# AD9959.net
KiCad netlist of a schematic drawn in Altium Designer
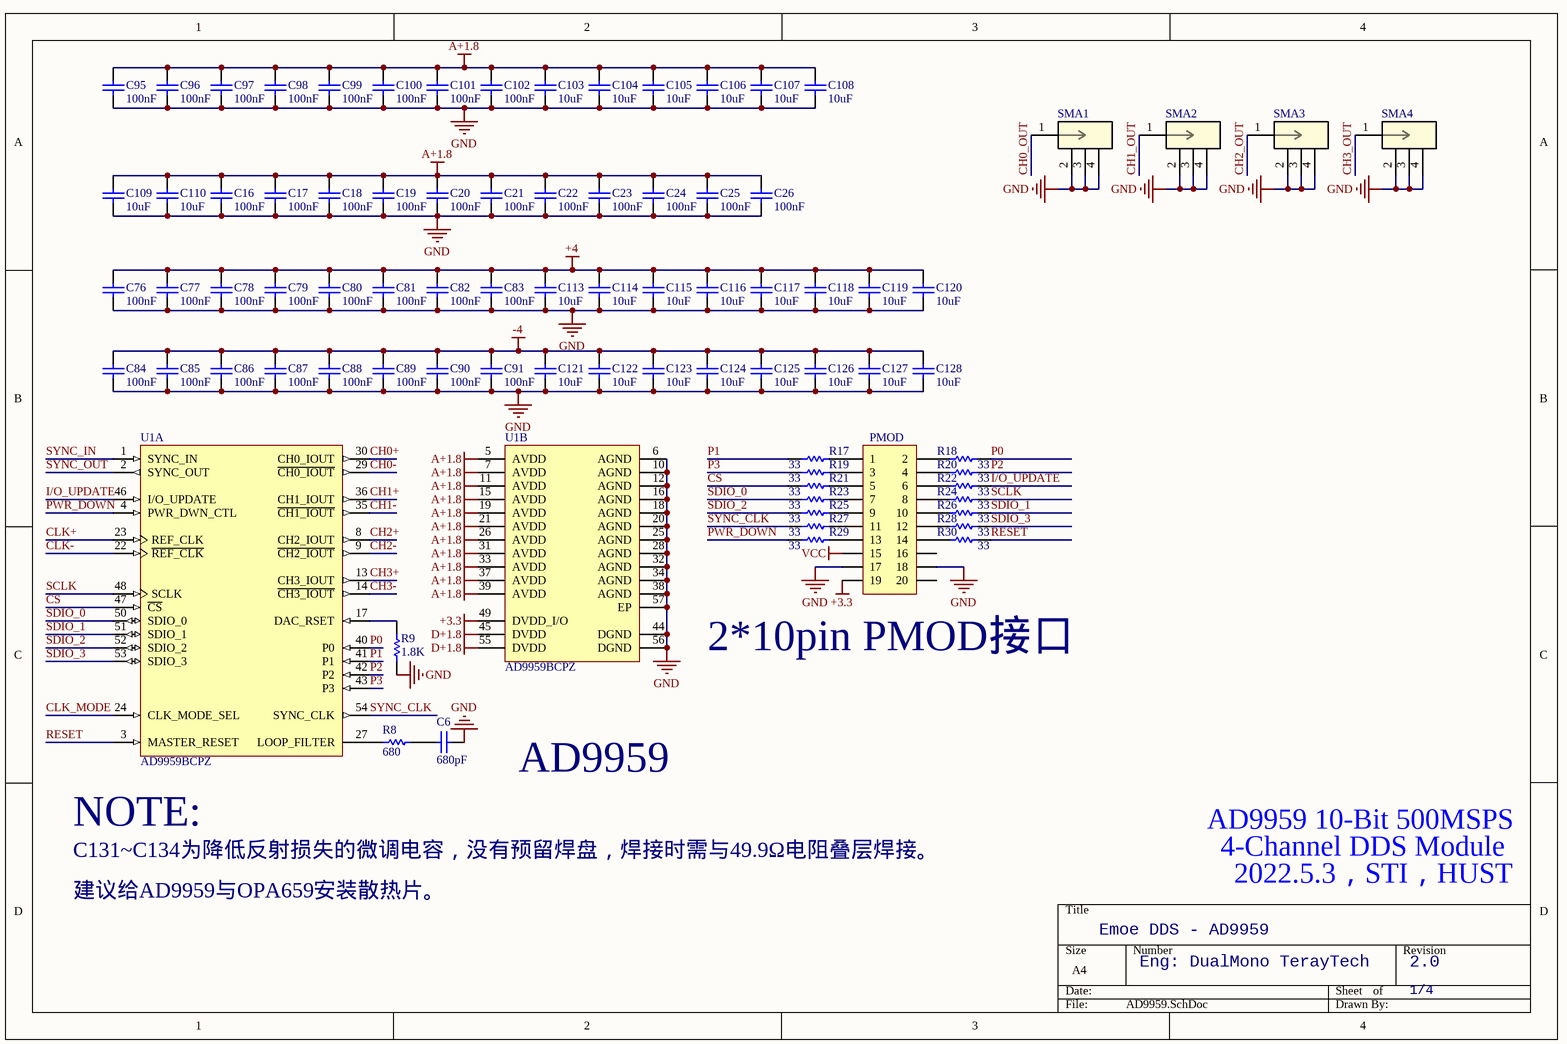
[diagram p0: AD9959.SchDoc]

(export (version "E")
  (design (tool "Eeschema 10.0.6"))
  (components
    (comp (ref "C6")
      (value "680pF")
      (footprint "0402")
      (description "Capacitor")
      (fields (field (name "PUBLISHER") "Altium Limited"))
      (libsource (lib "My Footprint") (part "CAP"))
    )
    (comp (ref "C16")
      (value "100nF")
      (footprint "0402")
      (description "Capacitor")
      (fields (field (name "PUBLISHER") "Altium Limited"))
      (libsource (lib "My Footprint") (part "CAP"))
    )
    (comp (ref "C17")
      (value "100nF")
      (footprint "0402")
      (description "Capacitor")
      (fields (field (name "PUBLISHER") "Altium Limited"))
      (libsource (lib "My Footprint") (part "CAP"))
    )
    (comp (ref "C18")
      (value "100nF")
      (footprint "0402")
      (description "Capacitor")
      (fields (field (name "PUBLISHER") "Altium Limited"))
      (libsource (lib "My Footprint") (part "CAP"))
    )
    (comp (ref "C19")
      (value "100nF")
      (footprint "0402")
      (description "Capacitor")
      (fields (field (name "PUBLISHER") "Altium Limited"))
      (libsource (lib "My Footprint") (part "CAP"))
    )
    (comp (ref "C20")
      (value "100nF")
      (footprint "0402")
      (description "Capacitor")
      (fields (field (name "PUBLISHER") "Altium Limited"))
      (libsource (lib "My Footprint") (part "CAP"))
    )
    (comp (ref "C21")
      (value "100nF")
      (footprint "0402")
      (description "Capacitor")
      (fields (field (name "PUBLISHER") "Altium Limited"))
      (libsource (lib "My Footprint") (part "CAP"))
    )
    (comp (ref "C22")
      (value "100nF")
      (footprint "0402")
      (description "Capacitor")
      (fields (field (name "PUBLISHER") "Altium Limited"))
      (libsource (lib "My Footprint") (part "CAP"))
    )
    (comp (ref "C23")
      (value "100nF")
      (footprint "0402")
      (description "Capacitor")
      (fields (field (name "PUBLISHER") "Altium Limited"))
      (libsource (lib "My Footprint") (part "CAP"))
    )
    (comp (ref "C24")
      (value "100nF")
      (footprint "0402")
      (description "Capacitor")
      (fields (field (name "PUBLISHER") "Altium Limited"))
      (libsource (lib "My Footprint") (part "CAP"))
    )
    (comp (ref "C25")
      (value "100nF")
      (footprint "0402")
      (description "Capacitor")
      (fields (field (name "PUBLISHER") "Altium Limited"))
      (libsource (lib "My Footprint") (part "CAP"))
    )
    (comp (ref "C26")
      (value "100nF")
      (footprint "0402")
      (description "Capacitor")
      (fields (field (name "PUBLISHER") "Altium Limited"))
      (libsource (lib "My Footprint") (part "CAP"))
    )
    (comp (ref "C76")
      (value "100nF")
      (footprint "0402")
      (description "Capacitor")
      (fields (field (name "PUBLISHER") "Altium Limited"))
      (libsource (lib "My Footprint") (part "CAP"))
    )
    (comp (ref "C77")
      (value "100nF")
      (footprint "0402")
      (description "Capacitor")
      (fields (field (name "PUBLISHER") "Altium Limited"))
      (libsource (lib "My Footprint") (part "CAP"))
    )
    (comp (ref "C78")
      (value "100nF")
      (footprint "0402")
      (description "Capacitor")
      (fields (field (name "PUBLISHER") "Altium Limited"))
      (libsource (lib "My Footprint") (part "CAP"))
    )
    (comp (ref "C79")
      (value "100nF")
      (footprint "0402")
      (description "Capacitor")
      (fields (field (name "PUBLISHER") "Altium Limited"))
      (libsource (lib "My Footprint") (part "CAP"))
    )
    (comp (ref "C80")
      (value "100nF")
      (footprint "0402")
      (description "Capacitor")
      (fields (field (name "PUBLISHER") "Altium Limited"))
      (libsource (lib "My Footprint") (part "CAP"))
    )
    (comp (ref "C81")
      (value "100nF")
      (footprint "0402")
      (description "Capacitor")
      (fields (field (name "PUBLISHER") "Altium Limited"))
      (libsource (lib "My Footprint") (part "CAP"))
    )
    (comp (ref "C82")
      (value "100nF")
      (footprint "0402")
      (description "Capacitor")
      (fields (field (name "PUBLISHER") "Altium Limited"))
      (libsource (lib "My Footprint") (part "CAP"))
    )
    (comp (ref "C83")
      (value "100nF")
      (footprint "0402")
      (description "Capacitor")
      (fields (field (name "PUBLISHER") "Altium Limited"))
      (libsource (lib "My Footprint") (part "CAP"))
    )
    (comp (ref "C84")
      (value "100nF")
      (footprint "0402")
      (description "Capacitor")
      (fields (field (name "PUBLISHER") "Altium Limited"))
      (libsource (lib "My Footprint") (part "CAP"))
    )
    (comp (ref "C85")
      (value "100nF")
      (footprint "0402")
      (description "Capacitor")
      (fields (field (name "PUBLISHER") "Altium Limited"))
      (libsource (lib "My Footprint") (part "CAP"))
    )
    (comp (ref "C86")
      (value "100nF")
      (footprint "0402")
      (description "Capacitor")
      (fields (field (name "PUBLISHER") "Altium Limited"))
      (libsource (lib "My Footprint") (part "CAP"))
    )
    (comp (ref "C87")
      (value "100nF")
      (footprint "0402")
      (description "Capacitor")
      (fields (field (name "PUBLISHER") "Altium Limited"))
      (libsource (lib "My Footprint") (part "CAP"))
    )
    (comp (ref "C88")
      (value "100nF")
      (footprint "0402")
      (description "Capacitor")
      (fields (field (name "PUBLISHER") "Altium Limited"))
      (libsource (lib "My Footprint") (part "CAP"))
    )
    (comp (ref "C89")
      (value "100nF")
      (footprint "0402")
      (description "Capacitor")
      (fields (field (name "PUBLISHER") "Altium Limited"))
      (libsource (lib "My Footprint") (part "CAP"))
    )
    (comp (ref "C90")
      (value "100nF")
      (footprint "0402")
      (description "Capacitor")
      (fields (field (name "PUBLISHER") "Altium Limited"))
      (libsource (lib "My Footprint") (part "CAP"))
    )
    (comp (ref "C91")
      (value "100nF")
      (footprint "0402")
      (description "Capacitor")
      (fields (field (name "PUBLISHER") "Altium Limited"))
      (libsource (lib "My Footprint") (part "CAP"))
    )
    (comp (ref "C95")
      (value "100nF")
      (footprint "0402")
      (description "Capacitor")
      (fields (field (name "PUBLISHER") "Altium Limited"))
      (libsource (lib "My Footprint") (part "CAP"))
    )
    (comp (ref "C96")
      (value "100nF")
      (footprint "0402")
      (description "Capacitor")
      (fields (field (name "PUBLISHER") "Altium Limited"))
      (libsource (lib "My Footprint") (part "CAP"))
    )
    (comp (ref "C97")
      (value "100nF")
      (footprint "0402")
      (description "Capacitor")
      (fields (field (name "PUBLISHER") "Altium Limited"))
      (libsource (lib "My Footprint") (part "CAP"))
    )
    (comp (ref "C98")
      (value "100nF")
      (footprint "0402")
      (description "Capacitor")
      (fields (field (name "PUBLISHER") "Altium Limited"))
      (libsource (lib "My Footprint") (part "CAP"))
    )
    (comp (ref "C99")
      (value "100nF")
      (footprint "0402")
      (description "Capacitor")
      (fields (field (name "PUBLISHER") "Altium Limited"))
      (libsource (lib "My Footprint") (part "CAP"))
    )
    (comp (ref "C100")
      (value "100nF")
      (footprint "0402")
      (description "Capacitor")
      (fields (field (name "PUBLISHER") "Altium Limited"))
      (libsource (lib "My Footprint") (part "CAP"))
    )
    (comp (ref "C101")
      (value "100nF")
      (footprint "0402")
      (description "Capacitor")
      (fields (field (name "PUBLISHER") "Altium Limited"))
      (libsource (lib "My Footprint") (part "CAP"))
    )
    (comp (ref "C102")
      (value "100nF")
      (footprint "0402")
      (description "Capacitor")
      (fields (field (name "PUBLISHER") "Altium Limited"))
      (libsource (lib "My Footprint") (part "CAP"))
    )
    (comp (ref "C103")
      (value "10uF")
      (footprint "0402")
      (description "Capacitor")
      (fields (field (name "PUBLISHER") "Altium Limited"))
      (libsource (lib "My Footprint") (part "CAP"))
    )
    (comp (ref "C104")
      (value "10uF")
      (footprint "0402")
      (description "Capacitor")
      (fields (field (name "PUBLISHER") "Altium Limited"))
      (libsource (lib "My Footprint") (part "CAP"))
    )
    (comp (ref "C105")
      (value "10uF")
      (footprint "0402")
      (description "Capacitor")
      (fields (field (name "PUBLISHER") "Altium Limited"))
      (libsource (lib "My Footprint") (part "CAP"))
    )
    (comp (ref "C106")
      (value "10uF")
      (footprint "0402")
      (description "Capacitor")
      (fields (field (name "PUBLISHER") "Altium Limited"))
      (libsource (lib "My Footprint") (part "CAP"))
    )
    (comp (ref "C107")
      (value "10uF")
      (footprint "0402")
      (description "Capacitor")
      (fields (field (name "PUBLISHER") "Altium Limited"))
      (libsource (lib "My Footprint") (part "CAP"))
    )
    (comp (ref "C108")
      (value "10uF")
      (footprint "0402")
      (description "Capacitor")
      (fields (field (name "PUBLISHER") "Altium Limited"))
      (libsource (lib "My Footprint") (part "CAP"))
    )
    (comp (ref "C109")
      (value "10uF")
      (footprint "0402")
      (description "Capacitor")
      (fields (field (name "PUBLISHER") "Altium Limited"))
      (libsource (lib "My Footprint") (part "CAP"))
    )
    (comp (ref "C110")
      (value "10uF")
      (footprint "0402")
      (description "Capacitor")
      (fields (field (name "PUBLISHER") "Altium Limited"))
      (libsource (lib "My Footprint") (part "CAP"))
    )
    (comp (ref "C113")
      (value "10uF")
      (footprint "0402")
      (description "Capacitor")
      (fields (field (name "PUBLISHER") "Altium Limited"))
      (libsource (lib "My Footprint") (part "CAP"))
    )
    (comp (ref "C114")
      (value "10uF")
      (footprint "0402")
      (description "Capacitor")
      (fields (field (name "PUBLISHER") "Altium Limited"))
      (libsource (lib "My Footprint") (part "CAP"))
    )
    (comp (ref "C115")
      (value "10uF")
      (footprint "0402")
      (description "Capacitor")
      (fields (field (name "PUBLISHER") "Altium Limited"))
      (libsource (lib "My Footprint") (part "CAP"))
    )
    (comp (ref "C116")
      (value "10uF")
      (footprint "0402")
      (description "Capacitor")
      (fields (field (name "PUBLISHER") "Altium Limited"))
      (libsource (lib "My Footprint") (part "CAP"))
    )
    (comp (ref "C117")
      (value "10uF")
      (footprint "0402")
      (description "Capacitor")
      (fields (field (name "PUBLISHER") "Altium Limited"))
      (libsource (lib "My Footprint") (part "CAP"))
    )
    (comp (ref "C118")
      (value "10uF")
      (footprint "0402")
      (description "Capacitor")
      (fields (field (name "PUBLISHER") "Altium Limited"))
      (libsource (lib "My Footprint") (part "CAP"))
    )
    (comp (ref "C119")
      (value "10uF")
      (footprint "0402")
      (description "Capacitor")
      (fields (field (name "PUBLISHER") "Altium Limited"))
      (libsource (lib "My Footprint") (part "CAP"))
    )
    (comp (ref "C120")
      (value "10uF")
      (footprint "0402")
      (description "Capacitor")
      (fields (field (name "PUBLISHER") "Altium Limited"))
      (libsource (lib "My Footprint") (part "CAP"))
    )
    (comp (ref "C121")
      (value "10uF")
      (footprint "0402")
      (description "Capacitor")
      (fields (field (name "PUBLISHER") "Altium Limited"))
      (libsource (lib "My Footprint") (part "CAP"))
    )
    (comp (ref "C122")
      (value "10uF")
      (footprint "0402")
      (description "Capacitor")
      (fields (field (name "PUBLISHER") "Altium Limited"))
      (libsource (lib "My Footprint") (part "CAP"))
    )
    (comp (ref "C123")
      (value "10uF")
      (footprint "0402")
      (description "Capacitor")
      (fields (field (name "PUBLISHER") "Altium Limited"))
      (libsource (lib "My Footprint") (part "CAP"))
    )
    (comp (ref "C124")
      (value "10uF")
      (footprint "0402")
      (description "Capacitor")
      (fields (field (name "PUBLISHER") "Altium Limited"))
      (libsource (lib "My Footprint") (part "CAP"))
    )
    (comp (ref "C125")
      (value "10uF")
      (footprint "0402")
      (description "Capacitor")
      (fields (field (name "PUBLISHER") "Altium Limited"))
      (libsource (lib "My Footprint") (part "CAP"))
    )
    (comp (ref "C126")
      (value "10uF")
      (footprint "0402")
      (description "Capacitor")
      (fields (field (name "PUBLISHER") "Altium Limited"))
      (libsource (lib "My Footprint") (part "CAP"))
    )
    (comp (ref "C127")
      (value "10uF")
      (footprint "0402")
      (description "Capacitor")
      (fields (field (name "PUBLISHER") "Altium Limited"))
      (libsource (lib "My Footprint") (part "CAP"))
    )
    (comp (ref "C128")
      (value "10uF")
      (footprint "0402")
      (description "Capacitor")
      (fields (field (name "PUBLISHER") "Altium Limited"))
      (libsource (lib "My Footprint") (part "CAP"))
    )
    (comp (ref "PMOD")
      (value "Header 2X10")
      (footprint "201R2X10")
      (description "10*2P接插件")
      (libsource (lib "2x10_PMOD") (part "Header 10X2"))
    )
    (comp (ref "R8")
      (value "680")
      (footprint "0402")
      (description "Resistor")
      (fields (field (name "PUBLISHER") "Altium Limited"))
      (libsource (lib "My Footprint") (part "RES"))
    )
    (comp (ref "R9")
      (value "1.8K")
      (footprint "0402")
      (description "Resistor")
      (fields (field (name "PUBLISHER") "Altium Limited"))
      (libsource (lib "My Footprint") (part "RES"))
    )
    (comp (ref "R17")
      (value "33")
      (footprint "0402")
      (description "Resistor")
      (fields (field (name "PUBLISHER") "Altium Limited"))
      (libsource (lib "My Footprint") (part "RES"))
    )
    (comp (ref "R18")
      (value "33")
      (footprint "0402")
      (description "Resistor")
      (fields (field (name "PUBLISHER") "Altium Limited"))
      (libsource (lib "My Footprint") (part "RES"))
    )
    (comp (ref "R19")
      (value "33")
      (footprint "0402")
      (description "Resistor")
      (fields (field (name "PUBLISHER") "Altium Limited"))
      (libsource (lib "My Footprint") (part "RES"))
    )
    (comp (ref "R20")
      (value "33")
      (footprint "0402")
      (description "Resistor")
      (fields (field (name "PUBLISHER") "Altium Limited"))
      (libsource (lib "My Footprint") (part "RES"))
    )
    (comp (ref "R21")
      (value "33")
      (footprint "0402")
      (description "Resistor")
      (fields (field (name "PUBLISHER") "Altium Limited"))
      (libsource (lib "My Footprint") (part "RES"))
    )
    (comp (ref "R22")
      (value "33")
      (footprint "0402")
      (description "Resistor")
      (fields (field (name "PUBLISHER") "Altium Limited"))
      (libsource (lib "My Footprint") (part "RES"))
    )
    (comp (ref "R23")
      (value "33")
      (footprint "0402")
      (description "Resistor")
      (fields (field (name "PUBLISHER") "Altium Limited"))
      (libsource (lib "My Footprint") (part "RES"))
    )
    (comp (ref "R24")
      (value "33")
      (footprint "0402")
      (description "Resistor")
      (fields (field (name "PUBLISHER") "Altium Limited"))
      (libsource (lib "My Footprint") (part "RES"))
    )
    (comp (ref "R25")
      (value "33")
      (footprint "0402")
      (description "Resistor")
      (fields (field (name "PUBLISHER") "Altium Limited"))
      (libsource (lib "My Footprint") (part "RES"))
    )
    (comp (ref "R26")
      (value "33")
      (footprint "0402")
      (description "Resistor")
      (fields (field (name "PUBLISHER") "Altium Limited"))
      (libsource (lib "My Footprint") (part "RES"))
    )
    (comp (ref "R27")
      (value "33")
      (footprint "0402")
      (description "Resistor")
      (fields (field (name "PUBLISHER") "Altium Limited"))
      (libsource (lib "My Footprint") (part "RES"))
    )
    (comp (ref "R28")
      (value "33")
      (footprint "0402")
      (description "Resistor")
      (fields (field (name "PUBLISHER") "Altium Limited"))
      (libsource (lib "My Footprint") (part "RES"))
    )
    (comp (ref "R29")
      (value "33")
      (footprint "0402")
      (description "Resistor")
      (fields (field (name "PUBLISHER") "Altium Limited"))
      (libsource (lib "My Footprint") (part "RES"))
    )
    (comp (ref "R30")
      (value "33")
      (footprint "0402")
      (description "Resistor")
      (fields (field (name "PUBLISHER") "Altium Limited"))
      (libsource (lib "My Footprint") (part "RES"))
    )
    (comp (ref "SMA1")
      (value "132414")
      (footprint "CONN_132414_AMP")
      (description "No Description Available")
      (fields (field (name "COPYRIGHT") "Copyright (C) 2022 Ultra Librarian. All rights reserved."))
      (libsource (lib "SMA_大偏脚_细针") (part "132414"))
    )
    (comp (ref "SMA2")
      (value "132414")
      (footprint "CONN_132414_AMP")
      (description "No Description Available")
      (fields (field (name "COPYRIGHT") "Copyright (C) 2022 Ultra Librarian. All rights reserved."))
      (libsource (lib "SMA_大偏脚_细针") (part "132414"))
    )
    (comp (ref "SMA3")
      (value "132414")
      (footprint "CONN_132414_AMP")
      (description "No Description Available")
      (fields (field (name "COPYRIGHT") "Copyright (C) 2022 Ultra Librarian. All rights reserved."))
      (libsource (lib "SMA_大偏脚_细针") (part "132414"))
    )
    (comp (ref "SMA4")
      (value "132414")
      (footprint "CONN_132414_AMP")
      (description "No Description Available")
      (fields (field (name "COPYRIGHT") "Copyright (C) 2022 Ultra Librarian. All rights reserved."))
      (libsource (lib "SMA_大偏脚_细针") (part "132414"))
    )
    (comp (ref "U1")
      (value "AD9959BCPZ")
      (footprint "ADI-CP-56-1_L")
      (description "4-Channel, 500 MSPS DDS with 10-Bit DACs, Serial, CP-56-1, 260 Tray, Pb-Free")
      (libsource (lib "AD9959") (part "CMP-0293-00014-1"))
    )
  )
  (nets
    (net (code "1") (name "+3.3") (class "Default")
      (node (ref "PMOD") (pin "19") (pinfunction "19_19") (pintype "passive"))
      (node (ref "U1") (pin "49") (pinfunction "DVDD_I/O_49") (pintype "power_in"))
    )
    (net (code "2") (name "+4") (class "Default")
      (node (ref "C113") (pin "1") (pinfunction "1_1") (pintype "passive"))
      (node (ref "C114") (pin "1") (pinfunction "1_1") (pintype "passive"))
      (node (ref "C115") (pin "1") (pinfunction "1_1") (pintype "passive"))
      (node (ref "C116") (pin "1") (pinfunction "1_1") (pintype "passive"))
      (node (ref "C117") (pin "1") (pinfunction "1_1") (pintype "passive"))
      (node (ref "C118") (pin "1") (pinfunction "1_1") (pintype "passive"))
      (node (ref "C119") (pin "1") (pinfunction "1_1") (pintype "passive"))
      (node (ref "C120") (pin "1") (pinfunction "1_1") (pintype "passive"))
      (node (ref "C76") (pin "1") (pinfunction "1_1") (pintype "passive"))
      (node (ref "C77") (pin "1") (pinfunction "1_1") (pintype "passive"))
      (node (ref "C78") (pin "1") (pinfunction "1_1") (pintype "passive"))
      (node (ref "C79") (pin "1") (pinfunction "1_1") (pintype "passive"))
      (node (ref "C80") (pin "1") (pinfunction "1_1") (pintype "passive"))
      (node (ref "C81") (pin "1") (pinfunction "1_1") (pintype "passive"))
      (node (ref "C82") (pin "1") (pinfunction "1_1") (pintype "passive"))
      (node (ref "C83") (pin "1") (pinfunction "1_1") (pintype "passive"))
    )
    (net (code "3") (name "-4") (class "Default")
      (node (ref "C121") (pin "1") (pinfunction "1_1") (pintype "passive"))
      (node (ref "C122") (pin "1") (pinfunction "1_1") (pintype "passive"))
      (node (ref "C123") (pin "1") (pinfunction "1_1") (pintype "passive"))
      (node (ref "C124") (pin "1") (pinfunction "1_1") (pintype "passive"))
      (node (ref "C125") (pin "1") (pinfunction "1_1") (pintype "passive"))
      (node (ref "C126") (pin "1") (pinfunction "1_1") (pintype "passive"))
      (node (ref "C127") (pin "1") (pinfunction "1_1") (pintype "passive"))
      (node (ref "C128") (pin "1") (pinfunction "1_1") (pintype "passive"))
      (node (ref "C84") (pin "1") (pinfunction "1_1") (pintype "passive"))
      (node (ref "C85") (pin "1") (pinfunction "1_1") (pintype "passive"))
      (node (ref "C86") (pin "1") (pinfunction "1_1") (pintype "passive"))
      (node (ref "C87") (pin "1") (pinfunction "1_1") (pintype "passive"))
      (node (ref "C88") (pin "1") (pinfunction "1_1") (pintype "passive"))
      (node (ref "C89") (pin "1") (pinfunction "1_1") (pintype "passive"))
      (node (ref "C90") (pin "1") (pinfunction "1_1") (pintype "passive"))
      (node (ref "C91") (pin "1") (pinfunction "1_1") (pintype "passive"))
    )
    (net (code "4") (name "/CH0+") (class "Default")
      (node (ref "U1") (pin "30") (pinfunction "CH0_IOUT_30") (pintype "output"))
    )
    (net (code "5") (name "/CH0-") (class "Default")
      (node (ref "U1") (pin "29") (pinfunction "~{CH0_IOUT}_29") (pintype "output"))
    )
    (net (code "6") (name "/CH0_OUT") (class "Default")
      (node (ref "SMA1") (pin "1") (pinfunction "1_1") (pintype "passive"))
    )
    (net (code "7") (name "/CH1+") (class "Default")
      (node (ref "U1") (pin "36") (pinfunction "CH1_IOUT_36") (pintype "output"))
    )
    (net (code "8") (name "/CH1-") (class "Default")
      (node (ref "U1") (pin "35") (pinfunction "~{CH1_IOUT}_35") (pintype "output"))
    )
    (net (code "9") (name "/CH1_OUT") (class "Default")
      (node (ref "SMA2") (pin "1") (pinfunction "1_1") (pintype "passive"))
    )
    (net (code "10") (name "/CH2+") (class "Default")
      (node (ref "U1") (pin "8") (pinfunction "CH2_IOUT_8") (pintype "output"))
    )
    (net (code "11") (name "/CH2-") (class "Default")
      (node (ref "U1") (pin "9") (pinfunction "~{CH2_IOUT}_9") (pintype "output"))
    )
    (net (code "12") (name "/CH2_OUT") (class "Default")
      (node (ref "SMA3") (pin "1") (pinfunction "1_1") (pintype "passive"))
    )
    (net (code "13") (name "/CH3+") (class "Default")
      (node (ref "U1") (pin "13") (pinfunction "CH3_IOUT_13") (pintype "output"))
    )
    (net (code "14") (name "/CH3-") (class "Default")
      (node (ref "U1") (pin "14") (pinfunction "~{CH3_IOUT}_14") (pintype "output"))
    )
    (net (code "15") (name "/CH3_OUT") (class "Default")
      (node (ref "SMA4") (pin "1") (pinfunction "1_1") (pintype "passive"))
    )
    (net (code "16") (name "/CLK+") (class "Default")
      (node (ref "U1") (pin "23") (pinfunction "REF_CLK_23") (pintype "input"))
    )
    (net (code "17") (name "/CLK-") (class "Default")
      (node (ref "U1") (pin "22") (pinfunction "~{REF_CLK}_22") (pintype "input"))
    )
    (net (code "18") (name "/CLK_MODE") (class "Default")
      (node (ref "U1") (pin "24") (pinfunction "CLK_MODE_SEL_24") (pintype "input"))
    )
    (net (code "19") (name "/CS") (class "Default")
      (node (ref "R21") (pin "2") (pinfunction "2_2") (pintype "passive"))
      (node (ref "U1") (pin "47") (pinfunction "~{CS}_47") (pintype "input"))
    )
    (net (code "20") (name "/I{slash}O_UPDATE") (class "Default")
      (node (ref "R22") (pin "1") (pinfunction "1_1") (pintype "passive"))
      (node (ref "U1") (pin "46") (pinfunction "I/O_UPDATE_46") (pintype "input"))
    )
    (net (code "21") (name "/P0") (class "Default")
      (node (ref "R18") (pin "1") (pinfunction "1_1") (pintype "passive"))
      (node (ref "U1") (pin "40") (pinfunction "P0_40") (pintype "input"))
    )
    (net (code "22") (name "/P1") (class "Default")
      (node (ref "R17") (pin "2") (pinfunction "2_2") (pintype "passive"))
      (node (ref "U1") (pin "41") (pinfunction "P1_41") (pintype "input"))
    )
    (net (code "23") (name "/P2") (class "Default")
      (node (ref "R20") (pin "1") (pinfunction "1_1") (pintype "passive"))
      (node (ref "U1") (pin "42") (pinfunction "P2_42") (pintype "input"))
    )
    (net (code "24") (name "/P3") (class "Default")
      (node (ref "R19") (pin "2") (pinfunction "2_2") (pintype "passive"))
      (node (ref "U1") (pin "43") (pinfunction "P3_43") (pintype "input"))
    )
    (net (code "25") (name "/PWR_DOWN") (class "Default")
      (node (ref "R29") (pin "2") (pinfunction "2_2") (pintype "passive"))
      (node (ref "U1") (pin "4") (pinfunction "PWR_DWN_CTL_4") (pintype "input"))
    )
    (net (code "26") (name "/RESET") (class "Default")
      (node (ref "R30") (pin "1") (pinfunction "1_1") (pintype "passive"))
      (node (ref "U1") (pin "3") (pinfunction "MASTER_RESET_3") (pintype "input"))
    )
    (net (code "27") (name "/SCLK") (class "Default")
      (node (ref "R24") (pin "1") (pinfunction "1_1") (pintype "passive"))
      (node (ref "U1") (pin "48") (pinfunction "SCLK_48") (pintype "input"))
    )
    (net (code "28") (name "/SDIO_0") (class "Default")
      (node (ref "R23") (pin "2") (pinfunction "2_2") (pintype "passive"))
      (node (ref "U1") (pin "50") (pinfunction "SDIO_0_50") (pintype "bidirectional"))
    )
    (net (code "29") (name "/SDIO_1") (class "Default")
      (node (ref "R26") (pin "1") (pinfunction "1_1") (pintype "passive"))
      (node (ref "U1") (pin "51") (pinfunction "SDIO_1_51") (pintype "bidirectional"))
    )
    (net (code "30") (name "/SDIO_2") (class "Default")
      (node (ref "R25") (pin "2") (pinfunction "2_2") (pintype "passive"))
      (node (ref "U1") (pin "52") (pinfunction "SDIO_2_52") (pintype "bidirectional"))
    )
    (net (code "31") (name "/SDIO_3") (class "Default")
      (node (ref "R28") (pin "1") (pinfunction "1_1") (pintype "passive"))
      (node (ref "U1") (pin "53") (pinfunction "SDIO_3_53") (pintype "bidirectional"))
    )
    (net (code "32") (name "/SYNC_CLK") (class "Default")
      (node (ref "R27") (pin "2") (pinfunction "2_2") (pintype "passive"))
      (node (ref "U1") (pin "54") (pinfunction "SYNC_CLK_54") (pintype "output"))
    )
    (net (code "33") (name "/SYNC_IN") (class "Default")
      (node (ref "U1") (pin "1") (pinfunction "SYNC_IN_1") (pintype "input"))
    )
    (net (code "34") (name "/SYNC_OUT") (class "Default")
      (node (ref "U1") (pin "2") (pinfunction "SYNC_OUT_2") (pintype "output"))
    )
    (net (code "35") (name "A+1.8") (class "Default")
      (node (ref "C100") (pin "1") (pinfunction "1_1") (pintype "passive"))
      (node (ref "C101") (pin "1") (pinfunction "1_1") (pintype "passive"))
      (node (ref "C102") (pin "1") (pinfunction "1_1") (pintype "passive"))
      (node (ref "C103") (pin "1") (pinfunction "1_1") (pintype "passive"))
      (node (ref "C104") (pin "1") (pinfunction "1_1") (pintype "passive"))
      (node (ref "C105") (pin "1") (pinfunction "1_1") (pintype "passive"))
      (node (ref "C106") (pin "1") (pinfunction "1_1") (pintype "passive"))
      (node (ref "C107") (pin "1") (pinfunction "1_1") (pintype "passive"))
      (node (ref "C108") (pin "1") (pinfunction "1_1") (pintype "passive"))
      (node (ref "C109") (pin "1") (pinfunction "1_1") (pintype "passive"))
      (node (ref "C110") (pin "1") (pinfunction "1_1") (pintype "passive"))
      (node (ref "C16") (pin "1") (pinfunction "1_1") (pintype "passive"))
      (node (ref "C17") (pin "1") (pinfunction "1_1") (pintype "passive"))
      (node (ref "C18") (pin "1") (pinfunction "1_1") (pintype "passive"))
      (node (ref "C19") (pin "1") (pinfunction "1_1") (pintype "passive"))
      (node (ref "C20") (pin "1") (pinfunction "1_1") (pintype "passive"))
      (node (ref "C21") (pin "1") (pinfunction "1_1") (pintype "passive"))
      (node (ref "C22") (pin "1") (pinfunction "1_1") (pintype "passive"))
      (node (ref "C23") (pin "1") (pinfunction "1_1") (pintype "passive"))
      (node (ref "C24") (pin "1") (pinfunction "1_1") (pintype "passive"))
      (node (ref "C25") (pin "1") (pinfunction "1_1") (pintype "passive"))
      (node (ref "C26") (pin "1") (pinfunction "1_1") (pintype "passive"))
      (node (ref "C95") (pin "1") (pinfunction "1_1") (pintype "passive"))
      (node (ref "C96") (pin "1") (pinfunction "1_1") (pintype "passive"))
      (node (ref "C97") (pin "1") (pinfunction "1_1") (pintype "passive"))
      (node (ref "C98") (pin "1") (pinfunction "1_1") (pintype "passive"))
      (node (ref "C99") (pin "1") (pinfunction "1_1") (pintype "passive"))
      (node (ref "U1") (pin "11") (pinfunction "AVDD_11") (pintype "power_in"))
      (node (ref "U1") (pin "15") (pinfunction "AVDD_15") (pintype "power_in"))
      (node (ref "U1") (pin "19") (pinfunction "AVDD_19") (pintype "power_in"))
      (node (ref "U1") (pin "21") (pinfunction "AVDD_21") (pintype "power_in"))
      (node (ref "U1") (pin "26") (pinfunction "AVDD_26") (pintype "power_in"))
      (node (ref "U1") (pin "31") (pinfunction "AVDD_31") (pintype "power_in"))
      (node (ref "U1") (pin "33") (pinfunction "AVDD_33") (pintype "power_in"))
      (node (ref "U1") (pin "37") (pinfunction "AVDD_37") (pintype "power_in"))
      (node (ref "U1") (pin "39") (pinfunction "AVDD_39") (pintype "power_in"))
      (node (ref "U1") (pin "5") (pinfunction "AVDD_5") (pintype "power_in"))
      (node (ref "U1") (pin "7") (pinfunction "AVDD_7") (pintype "power_in"))
    )
    (net (code "36") (name "D+1.8") (class "Default")
      (node (ref "U1") (pin "45") (pinfunction "DVDD_45") (pintype "power_in"))
      (node (ref "U1") (pin "55") (pinfunction "DVDD_55") (pintype "power_in"))
    )
    (net (code "37") (name "GND") (class "Default")
      (node (ref "C100") (pin "2") (pinfunction "2_2") (pintype "passive"))
      (node (ref "C101") (pin "2") (pinfunction "2_2") (pintype "passive"))
      (node (ref "C102") (pin "2") (pinfunction "2_2") (pintype "passive"))
      (node (ref "C103") (pin "2") (pinfunction "2_2") (pintype "passive"))
      (node (ref "C104") (pin "2") (pinfunction "2_2") (pintype "passive"))
      (node (ref "C105") (pin "2") (pinfunction "2_2") (pintype "passive"))
      (node (ref "C106") (pin "2") (pinfunction "2_2") (pintype "passive"))
      (node (ref "C107") (pin "2") (pinfunction "2_2") (pintype "passive"))
      (node (ref "C108") (pin "2") (pinfunction "2_2") (pintype "passive"))
      (node (ref "C109") (pin "2") (pinfunction "2_2") (pintype "passive"))
      (node (ref "C110") (pin "2") (pinfunction "2_2") (pintype "passive"))
      (node (ref "C113") (pin "2") (pinfunction "2_2") (pintype "passive"))
      (node (ref "C114") (pin "2") (pinfunction "2_2") (pintype "passive"))
      (node (ref "C115") (pin "2") (pinfunction "2_2") (pintype "passive"))
      (node (ref "C116") (pin "2") (pinfunction "2_2") (pintype "passive"))
      (node (ref "C117") (pin "2") (pinfunction "2_2") (pintype "passive"))
      (node (ref "C118") (pin "2") (pinfunction "2_2") (pintype "passive"))
      (node (ref "C119") (pin "2") (pinfunction "2_2") (pintype "passive"))
      (node (ref "C120") (pin "2") (pinfunction "2_2") (pintype "passive"))
      (node (ref "C121") (pin "2") (pinfunction "2_2") (pintype "passive"))
      (node (ref "C122") (pin "2") (pinfunction "2_2") (pintype "passive"))
      (node (ref "C123") (pin "2") (pinfunction "2_2") (pintype "passive"))
      (node (ref "C124") (pin "2") (pinfunction "2_2") (pintype "passive"))
      (node (ref "C125") (pin "2") (pinfunction "2_2") (pintype "passive"))
      (node (ref "C126") (pin "2") (pinfunction "2_2") (pintype "passive"))
      (node (ref "C127") (pin "2") (pinfunction "2_2") (pintype "passive"))
      (node (ref "C128") (pin "2") (pinfunction "2_2") (pintype "passive"))
      (node (ref "C16") (pin "2") (pinfunction "2_2") (pintype "passive"))
      (node (ref "C17") (pin "2") (pinfunction "2_2") (pintype "passive"))
      (node (ref "C18") (pin "2") (pinfunction "2_2") (pintype "passive"))
      (node (ref "C19") (pin "2") (pinfunction "2_2") (pintype "passive"))
      (node (ref "C20") (pin "2") (pinfunction "2_2") (pintype "passive"))
      (node (ref "C21") (pin "2") (pinfunction "2_2") (pintype "passive"))
      (node (ref "C22") (pin "2") (pinfunction "2_2") (pintype "passive"))
      (node (ref "C23") (pin "2") (pinfunction "2_2") (pintype "passive"))
      (node (ref "C24") (pin "2") (pinfunction "2_2") (pintype "passive"))
      (node (ref "C25") (pin "2") (pinfunction "2_2") (pintype "passive"))
      (node (ref "C26") (pin "2") (pinfunction "2_2") (pintype "passive"))
      (node (ref "C6") (pin "1") (pinfunction "1_1") (pintype "passive"))
      (node (ref "C76") (pin "2") (pinfunction "2_2") (pintype "passive"))
      (node (ref "C77") (pin "2") (pinfunction "2_2") (pintype "passive"))
      (node (ref "C78") (pin "2") (pinfunction "2_2") (pintype "passive"))
      (node (ref "C79") (pin "2") (pinfunction "2_2") (pintype "passive"))
      (node (ref "C80") (pin "2") (pinfunction "2_2") (pintype "passive"))
      (node (ref "C81") (pin "2") (pinfunction "2_2") (pintype "passive"))
      (node (ref "C82") (pin "2") (pinfunction "2_2") (pintype "passive"))
      (node (ref "C83") (pin "2") (pinfunction "2_2") (pintype "passive"))
      (node (ref "C84") (pin "2") (pinfunction "2_2") (pintype "passive"))
      (node (ref "C85") (pin "2") (pinfunction "2_2") (pintype "passive"))
      (node (ref "C86") (pin "2") (pinfunction "2_2") (pintype "passive"))
      (node (ref "C87") (pin "2") (pinfunction "2_2") (pintype "passive"))
      (node (ref "C88") (pin "2") (pinfunction "2_2") (pintype "passive"))
      (node (ref "C89") (pin "2") (pinfunction "2_2") (pintype "passive"))
      (node (ref "C90") (pin "2") (pinfunction "2_2") (pintype "passive"))
      (node (ref "C91") (pin "2") (pinfunction "2_2") (pintype "passive"))
      (node (ref "C95") (pin "2") (pinfunction "2_2") (pintype "passive"))
      (node (ref "C96") (pin "2") (pinfunction "2_2") (pintype "passive"))
      (node (ref "C97") (pin "2") (pinfunction "2_2") (pintype "passive"))
      (node (ref "C98") (pin "2") (pinfunction "2_2") (pintype "passive"))
      (node (ref "C99") (pin "2") (pinfunction "2_2") (pintype "passive"))
      (node (ref "PMOD") (pin "17") (pinfunction "17_17") (pintype "passive"))
      (node (ref "PMOD") (pin "18") (pinfunction "18_18") (pintype "passive"))
      (node (ref "R9") (pin "2") (pinfunction "2_2") (pintype "passive"))
      (node (ref "SMA1") (pin "2") (pinfunction "2_2") (pintype "passive"))
      (node (ref "SMA1") (pin "3") (pinfunction "3_3") (pintype "passive"))
      (node (ref "SMA1") (pin "4") (pinfunction "4_4") (pintype "passive"))
      (node (ref "SMA2") (pin "2") (pinfunction "2_2") (pintype "passive"))
      (node (ref "SMA2") (pin "3") (pinfunction "3_3") (pintype "passive"))
      (node (ref "SMA2") (pin "4") (pinfunction "4_4") (pintype "passive"))
      (node (ref "SMA3") (pin "2") (pinfunction "2_2") (pintype "passive"))
      (node (ref "SMA3") (pin "3") (pinfunction "3_3") (pintype "passive"))
      (node (ref "SMA3") (pin "4") (pinfunction "4_4") (pintype "passive"))
      (node (ref "SMA4") (pin "2") (pinfunction "2_2") (pintype "passive"))
      (node (ref "SMA4") (pin "3") (pinfunction "3_3") (pintype "passive"))
      (node (ref "SMA4") (pin "4") (pinfunction "4_4") (pintype "passive"))
      (node (ref "U1") (pin "10") (pinfunction "AGND_10") (pintype "power_in"))
      (node (ref "U1") (pin "12") (pinfunction "AGND_12") (pintype "power_in"))
      (node (ref "U1") (pin "16") (pinfunction "AGND_16") (pintype "power_in"))
      (node (ref "U1") (pin "18") (pinfunction "AGND_18") (pintype "power_in"))
      (node (ref "U1") (pin "20") (pinfunction "AGND_20") (pintype "power_in"))
      (node (ref "U1") (pin "25") (pinfunction "AGND_25") (pintype "power_in"))
      (node (ref "U1") (pin "28") (pinfunction "AGND_28") (pintype "power_in"))
      (node (ref "U1") (pin "32") (pinfunction "AGND_32") (pintype "power_in"))
      (node (ref "U1") (pin "34") (pinfunction "AGND_34") (pintype "power_in"))
      (node (ref "U1") (pin "38") (pinfunction "AGND_38") (pintype "power_in"))
      (node (ref "U1") (pin "44") (pinfunction "DGND_44") (pintype "power_in"))
      (node (ref "U1") (pin "56") (pinfunction "DGND_56") (pintype "power_in"))
      (node (ref "U1") (pin "57") (pinfunction "EP_57") (pintype "power_in"))
      (node (ref "U1") (pin "6") (pinfunction "AGND_6") (pintype "power_in"))
    )
    (net (code "38") (name "Net-(C6-Pad2)") (class "Default")
      (node (ref "C6") (pin "2") (pinfunction "2_2") (pintype "passive"))
      (node (ref "R8") (pin "2") (pinfunction "2_2") (pintype "passive"))
    )
    (net (code "39") (name "Net-(PMOD-Pad1)") (class "Default")
      (node (ref "PMOD") (pin "1") (pinfunction "1_1") (pintype "passive"))
      (node (ref "R17") (pin "1") (pinfunction "1_1") (pintype "passive"))
    )
    (net (code "40") (name "Net-(PMOD-Pad2)") (class "Default")
      (node (ref "PMOD") (pin "2") (pinfunction "2_2") (pintype "passive"))
      (node (ref "R18") (pin "2") (pinfunction "2_2") (pintype "passive"))
    )
    (net (code "41") (name "Net-(PMOD-Pad3)") (class "Default")
      (node (ref "PMOD") (pin "3") (pinfunction "3_3") (pintype "passive"))
      (node (ref "R19") (pin "1") (pinfunction "1_1") (pintype "passive"))
    )
    (net (code "42") (name "Net-(PMOD-Pad4)") (class "Default")
      (node (ref "PMOD") (pin "4") (pinfunction "4_4") (pintype "passive"))
      (node (ref "R20") (pin "2") (pinfunction "2_2") (pintype "passive"))
    )
    (net (code "43") (name "Net-(PMOD-Pad5)") (class "Default")
      (node (ref "PMOD") (pin "5") (pinfunction "5_5") (pintype "passive"))
      (node (ref "R21") (pin "1") (pinfunction "1_1") (pintype "passive"))
    )
    (net (code "44") (name "Net-(PMOD-Pad6)") (class "Default")
      (node (ref "PMOD") (pin "6") (pinfunction "6_6") (pintype "passive"))
      (node (ref "R22") (pin "2") (pinfunction "2_2") (pintype "passive"))
    )
    (net (code "45") (name "Net-(PMOD-Pad7)") (class "Default")
      (node (ref "PMOD") (pin "7") (pinfunction "7_7") (pintype "passive"))
      (node (ref "R23") (pin "1") (pinfunction "1_1") (pintype "passive"))
    )
    (net (code "46") (name "Net-(PMOD-Pad8)") (class "Default")
      (node (ref "PMOD") (pin "8") (pinfunction "8_8") (pintype "passive"))
      (node (ref "R24") (pin "2") (pinfunction "2_2") (pintype "passive"))
    )
    (net (code "47") (name "Net-(PMOD-Pad9)") (class "Default")
      (node (ref "PMOD") (pin "9") (pinfunction "9_9") (pintype "passive"))
      (node (ref "R25") (pin "1") (pinfunction "1_1") (pintype "passive"))
    )
    (net (code "48") (name "Net-(PMOD-Pad10)") (class "Default")
      (node (ref "PMOD") (pin "10") (pinfunction "10_10") (pintype "passive"))
      (node (ref "R26") (pin "2") (pinfunction "2_2") (pintype "passive"))
    )
    (net (code "49") (name "Net-(PMOD-Pad11)") (class "Default")
      (node (ref "PMOD") (pin "11") (pinfunction "11_11") (pintype "passive"))
      (node (ref "R27") (pin "1") (pinfunction "1_1") (pintype "passive"))
    )
    (net (code "50") (name "Net-(PMOD-Pad12)") (class "Default")
      (node (ref "PMOD") (pin "12") (pinfunction "12_12") (pintype "passive"))
      (node (ref "R28") (pin "2") (pinfunction "2_2") (pintype "passive"))
    )
    (net (code "51") (name "Net-(PMOD-Pad13)") (class "Default")
      (node (ref "PMOD") (pin "13") (pinfunction "13_13") (pintype "passive"))
      (node (ref "R29") (pin "1") (pinfunction "1_1") (pintype "passive"))
    )
    (net (code "52") (name "Net-(PMOD-Pad14)") (class "Default")
      (node (ref "PMOD") (pin "14") (pinfunction "14_14") (pintype "passive"))
      (node (ref "R30") (pin "2") (pinfunction "2_2") (pintype "passive"))
    )
    (net (code "53") (name "Net-(U1A-DAC_RSET)") (class "Default")
      (node (ref "R9") (pin "1") (pinfunction "1_1") (pintype "passive"))
      (node (ref "U1") (pin "17") (pinfunction "DAC_RSET_17") (pintype "input"))
    )
    (net (code "54") (name "Net-(U1A-LOOP_FILTER)") (class "Default")
      (node (ref "R8") (pin "1") (pinfunction "1_1") (pintype "passive"))
      (node (ref "U1") (pin "27") (pinfunction "LOOP_FILTER_27") (pintype "passive"))
    )
    (net (code "55") (name "VCC") (class "Default")
      (node (ref "PMOD") (pin "15") (pinfunction "15_15") (pintype "passive"))
    )
    (net (code "56") (name "unconnected-(PMOD-Pad16)") (class "Default")
      (node (ref "PMOD") (pin "16") (pinfunction "16_16") (pintype "passive"))
    )
    (net (code "57") (name "unconnected-(PMOD-Pad20)") (class "Default")
      (node (ref "PMOD") (pin "20") (pinfunction "20_20") (pintype "passive"))
    )
  )
)
